# Sheet1.net
KiCad netlist of a schematic drawn in Altium Designer
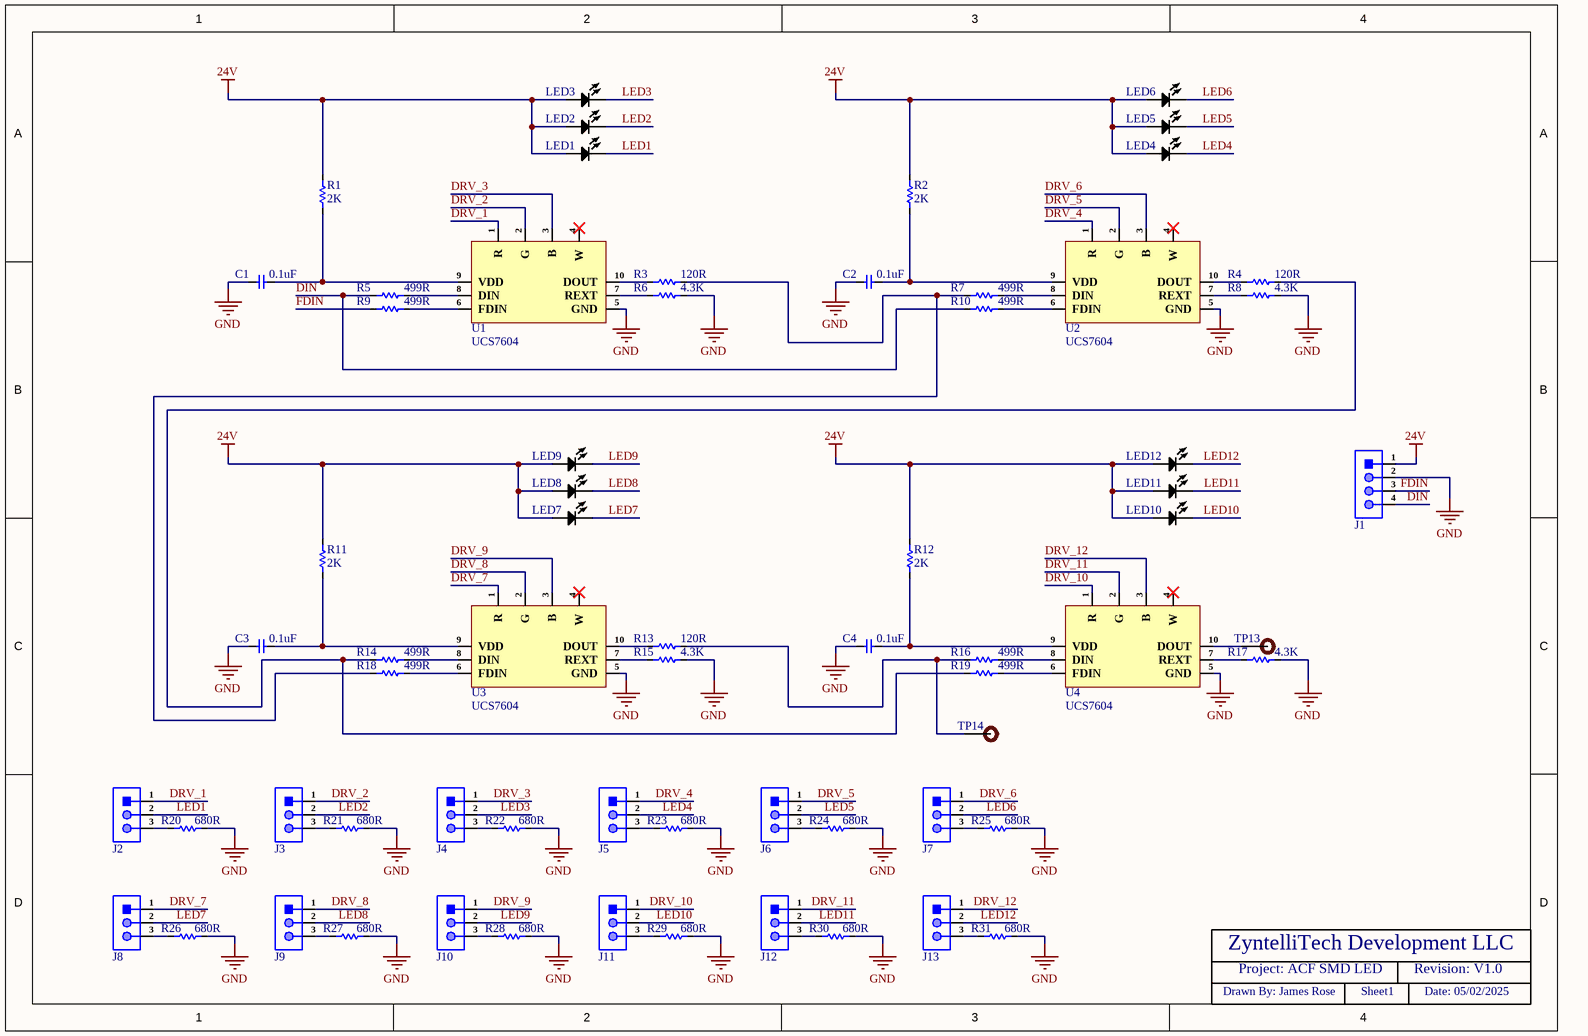
[diagram p0: Sheet1.SchDoc]

(export (version "E")
  (design (tool "Eeschema 10.0.6"))
  (components
    (comp (ref "C1")
      (value "0.1uF")
      (footprint "Cap-0603")
      (description "CAP CER 0.1UF 50V X7R 0603")
      (fields (field (name "LCSC PART NUMBER") "C91183") (field (name "MANUFACTURER") "Yageo"))
      (libsource (lib "eSpark Libraries") (part "CC0603JRX7R9BB104"))
    )
    (comp (ref "C2")
      (value "0.1uF")
      (footprint "Cap-0603")
      (description "CAP CER 0.1UF 50V X7R 0603")
      (fields (field (name "LCSC PART NUMBER") "C91183") (field (name "MANUFACTURER") "Yageo"))
      (libsource (lib "eSpark Libraries") (part "CC0603JRX7R9BB104"))
    )
    (comp (ref "C3")
      (value "0.1uF")
      (footprint "Cap-0603")
      (description "CAP CER 0.1UF 50V X7R 0603")
      (fields (field (name "LCSC PART NUMBER") "C91183") (field (name "MANUFACTURER") "Yageo"))
      (libsource (lib "eSpark Libraries") (part "CC0603JRX7R9BB104"))
    )
    (comp (ref "C4")
      (value "0.1uF")
      (footprint "Cap-0603")
      (description "CAP CER 0.1UF 50V X7R 0603")
      (fields (field (name "LCSC PART NUMBER") "C91183") (field (name "MANUFACTURER") "Yageo"))
      (libsource (lib "eSpark Libraries") (part "CC0603JRX7R9BB104"))
    )
    (comp (ref "J1")
      (value "X6511WV-04H-C60D30")
      (footprint "HDR1X4_")
      (fields (field (name "MANUFACTURER") "XKB") (field (name "LCSC PART NUMBER") "C706876"))
      (libsource (lib "eSpark Libraries") (part "X6511WV-04H-C60D30"))
    )
    (comp (ref "J2")
      (value "X6511WV-03H-C60D30")
      (footprint "HDR1X3_")
      (fields (field (name "MANUFACTURER") "XKB") (field (name "LCSC PART NUMBER") "C706875"))
      (libsource (lib "eSpark Libraries") (part "X6511WV-03H-C60D30"))
    )
    (comp (ref "J3")
      (value "X6511WV-03H-C60D30")
      (footprint "HDR1X3_")
      (fields (field (name "MANUFACTURER") "XKB") (field (name "LCSC PART NUMBER") "C706875"))
      (libsource (lib "eSpark Libraries") (part "X6511WV-03H-C60D30"))
    )
    (comp (ref "J4")
      (value "X6511WV-03H-C60D30")
      (footprint "HDR1X3_")
      (fields (field (name "MANUFACTURER") "XKB") (field (name "LCSC PART NUMBER") "C706875"))
      (libsource (lib "eSpark Libraries") (part "X6511WV-03H-C60D30"))
    )
    (comp (ref "J5")
      (value "X6511WV-03H-C60D30")
      (footprint "HDR1X3_")
      (fields (field (name "MANUFACTURER") "XKB") (field (name "LCSC PART NUMBER") "C706875"))
      (libsource (lib "eSpark Libraries") (part "X6511WV-03H-C60D30"))
    )
    (comp (ref "J6")
      (value "X6511WV-03H-C60D30")
      (footprint "HDR1X3_")
      (fields (field (name "MANUFACTURER") "XKB") (field (name "LCSC PART NUMBER") "C706875"))
      (libsource (lib "eSpark Libraries") (part "X6511WV-03H-C60D30"))
    )
    (comp (ref "J7")
      (value "X6511WV-03H-C60D30")
      (footprint "HDR1X3_")
      (fields (field (name "MANUFACTURER") "XKB") (field (name "LCSC PART NUMBER") "C706875"))
      (libsource (lib "eSpark Libraries") (part "X6511WV-03H-C60D30"))
    )
    (comp (ref "J8")
      (value "X6511WV-03H-C60D30")
      (footprint "HDR1X3_")
      (fields (field (name "MANUFACTURER") "XKB") (field (name "LCSC PART NUMBER") "C706875"))
      (libsource (lib "eSpark Libraries") (part "X6511WV-03H-C60D30"))
    )
    (comp (ref "J9")
      (value "X6511WV-03H-C60D30")
      (footprint "HDR1X3_")
      (fields (field (name "MANUFACTURER") "XKB") (field (name "LCSC PART NUMBER") "C706875"))
      (libsource (lib "eSpark Libraries") (part "X6511WV-03H-C60D30"))
    )
    (comp (ref "J10")
      (value "X6511WV-03H-C60D30")
      (footprint "HDR1X3_")
      (fields (field (name "MANUFACTURER") "XKB") (field (name "LCSC PART NUMBER") "C706875"))
      (libsource (lib "eSpark Libraries") (part "X6511WV-03H-C60D30"))
    )
    (comp (ref "J11")
      (value "X6511WV-03H-C60D30")
      (footprint "HDR1X3_")
      (fields (field (name "MANUFACTURER") "XKB") (field (name "LCSC PART NUMBER") "C706875"))
      (libsource (lib "eSpark Libraries") (part "X6511WV-03H-C60D30"))
    )
    (comp (ref "J12")
      (value "X6511WV-03H-C60D30")
      (footprint "HDR1X3_")
      (fields (field (name "MANUFACTURER") "XKB") (field (name "LCSC PART NUMBER") "C706875"))
      (libsource (lib "eSpark Libraries") (part "X6511WV-03H-C60D30"))
    )
    (comp (ref "J13")
      (value "X6511WV-03H-C60D30")
      (footprint "HDR1X3_")
      (fields (field (name "MANUFACTURER") "XKB") (field (name "LCSC PART NUMBER") "C706875"))
      (libsource (lib "eSpark Libraries") (part "X6511WV-03H-C60D30"))
    )
    (comp (ref "LED1")
      (value "5050 LED")
      (footprint "5050 LED")
      (libsource (lib "eSpark Libraries") (part "5050 LED"))
    )
    (comp (ref "LED2")
      (value "5050 LED")
      (footprint "5050 LED")
      (libsource (lib "eSpark Libraries") (part "5050 LED"))
    )
    (comp (ref "LED3")
      (value "5050 LED")
      (footprint "5050 LED")
      (libsource (lib "eSpark Libraries") (part "5050 LED"))
    )
    (comp (ref "LED4")
      (value "5050 LED")
      (footprint "5050 LED")
      (libsource (lib "eSpark Libraries") (part "5050 LED"))
    )
    (comp (ref "LED5")
      (value "5050 LED")
      (footprint "5050 LED")
      (libsource (lib "eSpark Libraries") (part "5050 LED"))
    )
    (comp (ref "LED6")
      (value "5050 LED")
      (footprint "5050 LED")
      (libsource (lib "eSpark Libraries") (part "5050 LED"))
    )
    (comp (ref "LED7")
      (value "5050 LED")
      (footprint "5050 LED")
      (libsource (lib "eSpark Libraries") (part "5050 LED"))
    )
    (comp (ref "LED8")
      (value "5050 LED")
      (footprint "5050 LED")
      (libsource (lib "eSpark Libraries") (part "5050 LED"))
    )
    (comp (ref "LED9")
      (value "5050 LED")
      (footprint "5050 LED")
      (libsource (lib "eSpark Libraries") (part "5050 LED"))
    )
    (comp (ref "LED10")
      (value "5050 LED")
      (footprint "5050 LED")
      (libsource (lib "eSpark Libraries") (part "5050 LED"))
    )
    (comp (ref "LED11")
      (value "5050 LED")
      (footprint "5050 LED")
      (libsource (lib "eSpark Libraries") (part "5050 LED"))
    )
    (comp (ref "LED12")
      (value "5050 LED")
      (footprint "5050 LED")
      (libsource (lib "eSpark Libraries") (part "5050 LED"))
    )
    (comp (ref "R1")
      (value "2K")
      (footprint "Res-1206")
      (description "RES 2K OHM 1% 1/4W 1206")
      (fields (field (name "LCSC PART NUMBER") "C133543") (field (name "MANUFACTURER") "Yageo"))
      (libsource (lib "eSpark Libraries") (part "RC1206FR-072KL"))
    )
    (comp (ref "R2")
      (value "2K")
      (footprint "Res-1206")
      (description "RES 2K OHM 1% 1/4W 1206")
      (fields (field (name "LCSC PART NUMBER") "C133543") (field (name "MANUFACTURER") "Yageo"))
      (libsource (lib "eSpark Libraries") (part "RC1206FR-072KL"))
    )
    (comp (ref "R3")
      (value "120R")
      (footprint "Res-0603")
      (description "RES 120 OHM 1% 1/10W 0603")
      (fields
        (field (name "MANUFACTURER") "Yageo")
        (field (name "MANUFACTURER PART NUMBER") "RC0603FR-07120RL")
      )
      (libsource (lib "eSpark Libraries") (part "RC0603FR-07120RL"))
    )
    (comp (ref "R4")
      (value "120R")
      (footprint "Res-0603")
      (description "RES 120 OHM 1% 1/10W 0603")
      (fields
        (field (name "MANUFACTURER") "Yageo")
        (field (name "MANUFACTURER PART NUMBER") "RC0603FR-07120RL")
      )
      (libsource (lib "eSpark Libraries") (part "RC0603FR-07120RL"))
    )
    (comp (ref "R5")
      (value "499R")
      (footprint "Res-0603")
      (description "RES 499 OHM 1% 1/10W 0603")
      (fields
        (field (name "MANUFACTURER") "Yageo")
        (field (name "MANUFACTURER PART NUMBER") "RC0603FR-07499RL")
      )
      (libsource (lib "eSpark Libraries") (part "RC0603FR-07499RL"))
    )
    (comp (ref "R6")
      (value "4.3K")
      (footprint "Res-0402")
      (description "RES 4.3K OHM 1% 1/16W 0402")
      (fields (field (name "LCSC PART NUMBER") "C477725") (field (name "MANUFACTURER") "Yageo"))
      (libsource (lib "eSpark Libraries") (part "RC0402FR-074K3L"))
    )
    (comp (ref "R7")
      (value "499R")
      (footprint "Res-0603")
      (description "RES 499 OHM 1% 1/10W 0603")
      (fields
        (field (name "MANUFACTURER") "Yageo")
        (field (name "MANUFACTURER PART NUMBER") "RC0603FR-07499RL")
      )
      (libsource (lib "eSpark Libraries") (part "RC0603FR-07499RL"))
    )
    (comp (ref "R8")
      (value "4.3K")
      (footprint "Res-0402")
      (description "RES 4.3K OHM 1% 1/16W 0402")
      (fields (field (name "LCSC PART NUMBER") "C477725") (field (name "MANUFACTURER") "Yageo"))
      (libsource (lib "eSpark Libraries") (part "RC0402FR-074K3L"))
    )
    (comp (ref "R9")
      (value "499R")
      (footprint "Res-0603")
      (description "RES 499 OHM 1% 1/10W 0603")
      (fields
        (field (name "MANUFACTURER") "Yageo")
        (field (name "MANUFACTURER PART NUMBER") "RC0603FR-07499RL")
      )
      (libsource (lib "eSpark Libraries") (part "RC0603FR-07499RL"))
    )
    (comp (ref "R10")
      (value "499R")
      (footprint "Res-0603")
      (description "RES 499 OHM 1% 1/10W 0603")
      (fields
        (field (name "MANUFACTURER") "Yageo")
        (field (name "MANUFACTURER PART NUMBER") "RC0603FR-07499RL")
      )
      (libsource (lib "eSpark Libraries") (part "RC0603FR-07499RL"))
    )
    (comp (ref "R11")
      (value "2K")
      (footprint "Res-1206")
      (description "RES 2K OHM 1% 1/4W 1206")
      (fields (field (name "LCSC PART NUMBER") "C133543") (field (name "MANUFACTURER") "Yageo"))
      (libsource (lib "eSpark Libraries") (part "RC1206FR-072KL"))
    )
    (comp (ref "R12")
      (value "2K")
      (footprint "Res-1206")
      (description "RES 2K OHM 1% 1/4W 1206")
      (fields (field (name "LCSC PART NUMBER") "C133543") (field (name "MANUFACTURER") "Yageo"))
      (libsource (lib "eSpark Libraries") (part "RC1206FR-072KL"))
    )
    (comp (ref "R13")
      (value "120R")
      (footprint "Res-0603")
      (description "RES 120 OHM 1% 1/10W 0603")
      (fields
        (field (name "MANUFACTURER") "Yageo")
        (field (name "MANUFACTURER PART NUMBER") "RC0603FR-07120RL")
      )
      (libsource (lib "eSpark Libraries") (part "RC0603FR-07120RL"))
    )
    (comp (ref "R14")
      (value "499R")
      (footprint "Res-0603")
      (description "RES 499 OHM 1% 1/10W 0603")
      (fields
        (field (name "MANUFACTURER") "Yageo")
        (field (name "MANUFACTURER PART NUMBER") "RC0603FR-07499RL")
      )
      (libsource (lib "eSpark Libraries") (part "RC0603FR-07499RL"))
    )
    (comp (ref "R15")
      (value "4.3K")
      (footprint "Res-0402")
      (description "RES 4.3K OHM 1% 1/16W 0402")
      (fields (field (name "LCSC PART NUMBER") "C477725") (field (name "MANUFACTURER") "Yageo"))
      (libsource (lib "eSpark Libraries") (part "RC0402FR-074K3L"))
    )
    (comp (ref "R16")
      (value "499R")
      (footprint "Res-0603")
      (description "RES 499 OHM 1% 1/10W 0603")
      (fields
        (field (name "MANUFACTURER") "Yageo")
        (field (name "MANUFACTURER PART NUMBER") "RC0603FR-07499RL")
      )
      (libsource (lib "eSpark Libraries") (part "RC0603FR-07499RL"))
    )
    (comp (ref "R17")
      (value "4.3K")
      (footprint "Res-0402")
      (description "RES 4.3K OHM 1% 1/16W 0402")
      (fields (field (name "LCSC PART NUMBER") "C477725") (field (name "MANUFACTURER") "Yageo"))
      (libsource (lib "eSpark Libraries") (part "RC0402FR-074K3L"))
    )
    (comp (ref "R18")
      (value "499R")
      (footprint "Res-0603")
      (description "RES 499 OHM 1% 1/10W 0603")
      (fields
        (field (name "MANUFACTURER") "Yageo")
        (field (name "MANUFACTURER PART NUMBER") "RC0603FR-07499RL")
      )
      (libsource (lib "eSpark Libraries") (part "RC0603FR-07499RL"))
    )
    (comp (ref "R19")
      (value "499R")
      (footprint "Res-0603")
      (description "RES 499 OHM 1% 1/10W 0603")
      (fields
        (field (name "MANUFACTURER") "Yageo")
        (field (name "MANUFACTURER PART NUMBER") "RC0603FR-07499RL")
      )
      (libsource (lib "eSpark Libraries") (part "RC0603FR-07499RL"))
    )
    (comp (ref "R20")
      (value "680R")
      (footprint "Res-0603")
      (description "RES SMD 680 OHM 1% 1/10W 0603")
      (fields
        (field (name "MANUFACTURER") "Yageo")
        (field (name "MANUFACTURER PART NUMBER") "RC0603FR-07680RL")
      )
      (libsource (lib "eSpark Libraries") (part "RC0603FR-07680RL"))
    )
    (comp (ref "R21")
      (value "680R")
      (footprint "Res-0603")
      (description "RES SMD 680 OHM 1% 1/10W 0603")
      (fields
        (field (name "MANUFACTURER") "Yageo")
        (field (name "MANUFACTURER PART NUMBER") "RC0603FR-07680RL")
      )
      (libsource (lib "eSpark Libraries") (part "RC0603FR-07680RL"))
    )
    (comp (ref "R22")
      (value "680R")
      (footprint "Res-0603")
      (description "RES SMD 680 OHM 1% 1/10W 0603")
      (fields
        (field (name "MANUFACTURER") "Yageo")
        (field (name "MANUFACTURER PART NUMBER") "RC0603FR-07680RL")
      )
      (libsource (lib "eSpark Libraries") (part "RC0603FR-07680RL"))
    )
    (comp (ref "R23")
      (value "680R")
      (footprint "Res-0603")
      (description "RES SMD 680 OHM 1% 1/10W 0603")
      (fields
        (field (name "MANUFACTURER") "Yageo")
        (field (name "MANUFACTURER PART NUMBER") "RC0603FR-07680RL")
      )
      (libsource (lib "eSpark Libraries") (part "RC0603FR-07680RL"))
    )
    (comp (ref "R24")
      (value "680R")
      (footprint "Res-0603")
      (description "RES SMD 680 OHM 1% 1/10W 0603")
      (fields
        (field (name "MANUFACTURER") "Yageo")
        (field (name "MANUFACTURER PART NUMBER") "RC0603FR-07680RL")
      )
      (libsource (lib "eSpark Libraries") (part "RC0603FR-07680RL"))
    )
    (comp (ref "R25")
      (value "680R")
      (footprint "Res-0603")
      (description "RES SMD 680 OHM 1% 1/10W 0603")
      (fields
        (field (name "MANUFACTURER") "Yageo")
        (field (name "MANUFACTURER PART NUMBER") "RC0603FR-07680RL")
      )
      (libsource (lib "eSpark Libraries") (part "RC0603FR-07680RL"))
    )
    (comp (ref "R26")
      (value "680R")
      (footprint "Res-0603")
      (description "RES SMD 680 OHM 1% 1/10W 0603")
      (fields
        (field (name "MANUFACTURER") "Yageo")
        (field (name "MANUFACTURER PART NUMBER") "RC0603FR-07680RL")
      )
      (libsource (lib "eSpark Libraries") (part "RC0603FR-07680RL"))
    )
    (comp (ref "R27")
      (value "680R")
      (footprint "Res-0603")
      (description "RES SMD 680 OHM 1% 1/10W 0603")
      (fields
        (field (name "MANUFACTURER") "Yageo")
        (field (name "MANUFACTURER PART NUMBER") "RC0603FR-07680RL")
      )
      (libsource (lib "eSpark Libraries") (part "RC0603FR-07680RL"))
    )
    (comp (ref "R28")
      (value "680R")
      (footprint "Res-0603")
      (description "RES SMD 680 OHM 1% 1/10W 0603")
      (fields
        (field (name "MANUFACTURER") "Yageo")
        (field (name "MANUFACTURER PART NUMBER") "RC0603FR-07680RL")
      )
      (libsource (lib "eSpark Libraries") (part "RC0603FR-07680RL"))
    )
    (comp (ref "R29")
      (value "680R")
      (footprint "Res-0603")
      (description "RES SMD 680 OHM 1% 1/10W 0603")
      (fields
        (field (name "MANUFACTURER") "Yageo")
        (field (name "MANUFACTURER PART NUMBER") "RC0603FR-07680RL")
      )
      (libsource (lib "eSpark Libraries") (part "RC0603FR-07680RL"))
    )
    (comp (ref "R30")
      (value "680R")
      (footprint "Res-0603")
      (description "RES SMD 680 OHM 1% 1/10W 0603")
      (fields
        (field (name "MANUFACTURER") "Yageo")
        (field (name "MANUFACTURER PART NUMBER") "RC0603FR-07680RL")
      )
      (libsource (lib "eSpark Libraries") (part "RC0603FR-07680RL"))
    )
    (comp (ref "R31")
      (value "680R")
      (footprint "Res-0603")
      (description "RES SMD 680 OHM 1% 1/10W 0603")
      (fields
        (field (name "MANUFACTURER") "Yageo")
        (field (name "MANUFACTURER PART NUMBER") "RC0603FR-07680RL")
      )
      (libsource (lib "eSpark Libraries") (part "RC0603FR-07680RL"))
    )
    (comp (ref "TP13")
      (value "0.5mm Test Pad")
      (footprint "0.5mm Test Pad")
      (description "Test pad")
      (libsource (lib "eSpark Libraries") (part "0.5mm Test Pad"))
    )
    (comp (ref "TP14")
      (value "0.5mm Test Pad")
      (footprint "0.5mm Test Pad")
      (description "Test pad")
      (libsource (lib "eSpark Libraries") (part "0.5mm Test Pad"))
    )
    (comp (ref "U1")
      (value "UCS7604")
      (footprint "SOP-10")
      (description "RGBW LED Driver")
      (fields (field (name "MANUFACTURER") "UCS"))
      (libsource (lib "eSpark Libraries") (part "UCS7604"))
    )
    (comp (ref "U2")
      (value "UCS7604")
      (footprint "SOP-10")
      (description "RGBW LED Driver")
      (fields (field (name "MANUFACTURER") "UCS"))
      (libsource (lib "eSpark Libraries") (part "UCS7604"))
    )
    (comp (ref "U3")
      (value "UCS7604")
      (footprint "SOP-10")
      (description "RGBW LED Driver")
      (fields (field (name "MANUFACTURER") "UCS"))
      (libsource (lib "eSpark Libraries") (part "UCS7604"))
    )
    (comp (ref "U4")
      (value "UCS7604")
      (footprint "SOP-10")
      (description "RGBW LED Driver")
      (fields (field (name "MANUFACTURER") "UCS"))
      (libsource (lib "eSpark Libraries") (part "UCS7604"))
    )
  )
  (nets
    (net (code "1") (name "/DIN") (class "Default")
      (node (ref "J1") (pin "4") (pinfunction "4_4") (pintype "passive"))
      (node (ref "R10") (pin "1") (pinfunction "1_1") (pintype "passive"))
      (node (ref "R5") (pin "1") (pinfunction "1_1") (pintype "passive"))
    )
    (net (code "2") (name "/DRV_1") (class "Default")
      (node (ref "J2") (pin "1") (pinfunction "1_1") (pintype "passive"))
      (node (ref "U1") (pin "1") (pinfunction "R_1") (pintype "passive"))
    )
    (net (code "3") (name "/DRV_2") (class "Default")
      (node (ref "J3") (pin "1") (pinfunction "1_1") (pintype "passive"))
      (node (ref "U1") (pin "2") (pinfunction "G_2") (pintype "passive"))
    )
    (net (code "4") (name "/DRV_3") (class "Default")
      (node (ref "J4") (pin "1") (pinfunction "1_1") (pintype "passive"))
      (node (ref "U1") (pin "3") (pinfunction "B_3") (pintype "passive"))
    )
    (net (code "5") (name "/DRV_4") (class "Default")
      (node (ref "J5") (pin "1") (pinfunction "1_1") (pintype "passive"))
      (node (ref "U2") (pin "1") (pinfunction "R_1") (pintype "passive"))
    )
    (net (code "6") (name "/DRV_5") (class "Default")
      (node (ref "J6") (pin "1") (pinfunction "1_1") (pintype "passive"))
      (node (ref "U2") (pin "2") (pinfunction "G_2") (pintype "passive"))
    )
    (net (code "7") (name "/DRV_6") (class "Default")
      (node (ref "J7") (pin "1") (pinfunction "1_1") (pintype "passive"))
      (node (ref "U2") (pin "3") (pinfunction "B_3") (pintype "passive"))
    )
    (net (code "8") (name "/DRV_7") (class "Default")
      (node (ref "J8") (pin "1") (pinfunction "1_1") (pintype "passive"))
      (node (ref "U3") (pin "1") (pinfunction "R_1") (pintype "passive"))
    )
    (net (code "9") (name "/DRV_8") (class "Default")
      (node (ref "J9") (pin "1") (pinfunction "1_1") (pintype "passive"))
      (node (ref "U3") (pin "2") (pinfunction "G_2") (pintype "passive"))
    )
    (net (code "10") (name "/DRV_9") (class "Default")
      (node (ref "J10") (pin "1") (pinfunction "1_1") (pintype "passive"))
      (node (ref "U3") (pin "3") (pinfunction "B_3") (pintype "passive"))
    )
    (net (code "11") (name "/DRV_10") (class "Default")
      (node (ref "J11") (pin "1") (pinfunction "1_1") (pintype "passive"))
      (node (ref "U4") (pin "1") (pinfunction "R_1") (pintype "passive"))
    )
    (net (code "12") (name "/DRV_11") (class "Default")
      (node (ref "J12") (pin "1") (pinfunction "1_1") (pintype "passive"))
      (node (ref "U4") (pin "2") (pinfunction "G_2") (pintype "passive"))
    )
    (net (code "13") (name "/DRV_12") (class "Default")
      (node (ref "J13") (pin "1") (pinfunction "1_1") (pintype "passive"))
      (node (ref "U4") (pin "3") (pinfunction "B_3") (pintype "passive"))
    )
    (net (code "14") (name "/FDIN") (class "Default")
      (node (ref "J1") (pin "3") (pinfunction "3_3") (pintype "passive"))
      (node (ref "R9") (pin "1") (pinfunction "1_1") (pintype "passive"))
    )
    (net (code "15") (name "/LED1") (class "Default")
      (node (ref "J2") (pin "2") (pinfunction "2_2") (pintype "passive"))
      (node (ref "LED1") (pin "K") (pinfunction "K_K") (pintype "passive"))
    )
    (net (code "16") (name "/LED2") (class "Default")
      (node (ref "J3") (pin "2") (pinfunction "2_2") (pintype "passive"))
      (node (ref "LED2") (pin "K") (pinfunction "K_K") (pintype "passive"))
    )
    (net (code "17") (name "/LED3") (class "Default")
      (node (ref "J4") (pin "2") (pinfunction "2_2") (pintype "passive"))
      (node (ref "LED3") (pin "K") (pinfunction "K_K") (pintype "passive"))
    )
    (net (code "18") (name "/LED4") (class "Default")
      (node (ref "J5") (pin "2") (pinfunction "2_2") (pintype "passive"))
      (node (ref "LED4") (pin "K") (pinfunction "K_K") (pintype "passive"))
    )
    (net (code "19") (name "/LED5") (class "Default")
      (node (ref "J6") (pin "2") (pinfunction "2_2") (pintype "passive"))
      (node (ref "LED5") (pin "K") (pinfunction "K_K") (pintype "passive"))
    )
    (net (code "20") (name "/LED6") (class "Default")
      (node (ref "J7") (pin "2") (pinfunction "2_2") (pintype "passive"))
      (node (ref "LED6") (pin "K") (pinfunction "K_K") (pintype "passive"))
    )
    (net (code "21") (name "/LED7") (class "Default")
      (node (ref "J8") (pin "2") (pinfunction "2_2") (pintype "passive"))
      (node (ref "LED7") (pin "K") (pinfunction "K_K") (pintype "passive"))
    )
    (net (code "22") (name "/LED8") (class "Default")
      (node (ref "J9") (pin "2") (pinfunction "2_2") (pintype "passive"))
      (node (ref "LED8") (pin "K") (pinfunction "K_K") (pintype "passive"))
    )
    (net (code "23") (name "/LED9") (class "Default")
      (node (ref "J10") (pin "2") (pinfunction "2_2") (pintype "passive"))
      (node (ref "LED9") (pin "K") (pinfunction "K_K") (pintype "passive"))
    )
    (net (code "24") (name "/LED10") (class "Default")
      (node (ref "J11") (pin "2") (pinfunction "2_2") (pintype "passive"))
      (node (ref "LED10") (pin "K") (pinfunction "K_K") (pintype "passive"))
    )
    (net (code "25") (name "/LED11") (class "Default")
      (node (ref "J12") (pin "2") (pinfunction "2_2") (pintype "passive"))
      (node (ref "LED11") (pin "K") (pinfunction "K_K") (pintype "passive"))
    )
    (net (code "26") (name "/LED12") (class "Default")
      (node (ref "J13") (pin "2") (pinfunction "2_2") (pintype "passive"))
      (node (ref "LED12") (pin "K") (pinfunction "K_K") (pintype "passive"))
    )
    (net (code "27") (name "24V") (class "Default")
      (node (ref "J1") (pin "1") (pinfunction "1_1") (pintype "passive"))
      (node (ref "LED1") (pin "A") (pinfunction "A_A") (pintype "passive"))
      (node (ref "LED10") (pin "A") (pinfunction "A_A") (pintype "passive"))
      (node (ref "LED11") (pin "A") (pinfunction "A_A") (pintype "passive"))
      (node (ref "LED12") (pin "A") (pinfunction "A_A") (pintype "passive"))
      (node (ref "LED2") (pin "A") (pinfunction "A_A") (pintype "passive"))
      (node (ref "LED3") (pin "A") (pinfunction "A_A") (pintype "passive"))
      (node (ref "LED4") (pin "A") (pinfunction "A_A") (pintype "passive"))
      (node (ref "LED5") (pin "A") (pinfunction "A_A") (pintype "passive"))
      (node (ref "LED6") (pin "A") (pinfunction "A_A") (pintype "passive"))
      (node (ref "LED7") (pin "A") (pinfunction "A_A") (pintype "passive"))
      (node (ref "LED8") (pin "A") (pinfunction "A_A") (pintype "passive"))
      (node (ref "LED9") (pin "A") (pinfunction "A_A") (pintype "passive"))
      (node (ref "R1") (pin "2") (pinfunction "2_2") (pintype "passive"))
      (node (ref "R11") (pin "2") (pinfunction "2_2") (pintype "passive"))
      (node (ref "R12") (pin "2") (pinfunction "2_2") (pintype "passive"))
      (node (ref "R2") (pin "2") (pinfunction "2_2") (pintype "passive"))
    )
    (net (code "28") (name "GND") (class "Default")
      (node (ref "C1") (pin "1") (pinfunction "1_1") (pintype "passive"))
      (node (ref "C2") (pin "1") (pinfunction "1_1") (pintype "passive"))
      (node (ref "C3") (pin "1") (pinfunction "1_1") (pintype "passive"))
      (node (ref "C4") (pin "1") (pinfunction "1_1") (pintype "passive"))
      (node (ref "J1") (pin "2") (pinfunction "2_2") (pintype "passive"))
      (node (ref "R15") (pin "2") (pinfunction "2_2") (pintype "passive"))
      (node (ref "R17") (pin "2") (pinfunction "2_2") (pintype "passive"))
      (node (ref "R20") (pin "2") (pinfunction "2_2") (pintype "passive"))
      (node (ref "R21") (pin "2") (pinfunction "2_2") (pintype "passive"))
      (node (ref "R22") (pin "2") (pinfunction "2_2") (pintype "passive"))
      (node (ref "R23") (pin "2") (pinfunction "2_2") (pintype "passive"))
      (node (ref "R24") (pin "2") (pinfunction "2_2") (pintype "passive"))
      (node (ref "R25") (pin "2") (pinfunction "2_2") (pintype "passive"))
      (node (ref "R26") (pin "2") (pinfunction "2_2") (pintype "passive"))
      (node (ref "R27") (pin "2") (pinfunction "2_2") (pintype "passive"))
      (node (ref "R28") (pin "2") (pinfunction "2_2") (pintype "passive"))
      (node (ref "R29") (pin "2") (pinfunction "2_2") (pintype "passive"))
      (node (ref "R30") (pin "2") (pinfunction "2_2") (pintype "passive"))
      (node (ref "R31") (pin "2") (pinfunction "2_2") (pintype "passive"))
      (node (ref "R6") (pin "2") (pinfunction "2_2") (pintype "passive"))
      (node (ref "R8") (pin "2") (pinfunction "2_2") (pintype "passive"))
      (node (ref "U1") (pin "5") (pinfunction "GND_5") (pintype "passive"))
      (node (ref "U2") (pin "5") (pinfunction "GND_5") (pintype "passive"))
      (node (ref "U3") (pin "5") (pinfunction "GND_5") (pintype "passive"))
      (node (ref "U4") (pin "5") (pinfunction "GND_5") (pintype "passive"))
    )
    (net (code "29") (name "Net-(J2-Pad3)") (class "Default")
      (node (ref "J2") (pin "3") (pinfunction "3_3") (pintype "passive"))
      (node (ref "R20") (pin "1") (pinfunction "1_1") (pintype "passive"))
    )
    (net (code "30") (name "Net-(J3-Pad3)") (class "Default")
      (node (ref "J3") (pin "3") (pinfunction "3_3") (pintype "passive"))
      (node (ref "R21") (pin "1") (pinfunction "1_1") (pintype "passive"))
    )
    (net (code "31") (name "Net-(J4-Pad3)") (class "Default")
      (node (ref "J4") (pin "3") (pinfunction "3_3") (pintype "passive"))
      (node (ref "R22") (pin "1") (pinfunction "1_1") (pintype "passive"))
    )
    (net (code "32") (name "Net-(J5-Pad3)") (class "Default")
      (node (ref "J5") (pin "3") (pinfunction "3_3") (pintype "passive"))
      (node (ref "R23") (pin "1") (pinfunction "1_1") (pintype "passive"))
    )
    (net (code "33") (name "Net-(J6-Pad3)") (class "Default")
      (node (ref "J6") (pin "3") (pinfunction "3_3") (pintype "passive"))
      (node (ref "R24") (pin "1") (pinfunction "1_1") (pintype "passive"))
    )
    (net (code "34") (name "Net-(J7-Pad3)") (class "Default")
      (node (ref "J7") (pin "3") (pinfunction "3_3") (pintype "passive"))
      (node (ref "R25") (pin "1") (pinfunction "1_1") (pintype "passive"))
    )
    (net (code "35") (name "Net-(J8-Pad3)") (class "Default")
      (node (ref "J8") (pin "3") (pinfunction "3_3") (pintype "passive"))
      (node (ref "R26") (pin "1") (pinfunction "1_1") (pintype "passive"))
    )
    (net (code "36") (name "Net-(J9-Pad3)") (class "Default")
      (node (ref "J9") (pin "3") (pinfunction "3_3") (pintype "passive"))
      (node (ref "R27") (pin "1") (pinfunction "1_1") (pintype "passive"))
    )
    (net (code "37") (name "Net-(J10-Pad3)") (class "Default")
      (node (ref "J10") (pin "3") (pinfunction "3_3") (pintype "passive"))
      (node (ref "R28") (pin "1") (pinfunction "1_1") (pintype "passive"))
    )
    (net (code "38") (name "Net-(J11-Pad3)") (class "Default")
      (node (ref "J11") (pin "3") (pinfunction "3_3") (pintype "passive"))
      (node (ref "R29") (pin "1") (pinfunction "1_1") (pintype "passive"))
    )
    (net (code "39") (name "Net-(J12-Pad3)") (class "Default")
      (node (ref "J12") (pin "3") (pinfunction "3_3") (pintype "passive"))
      (node (ref "R30") (pin "1") (pinfunction "1_1") (pintype "passive"))
    )
    (net (code "40") (name "Net-(J13-Pad3)") (class "Default")
      (node (ref "J13") (pin "3") (pinfunction "3_3") (pintype "passive"))
      (node (ref "R31") (pin "1") (pinfunction "1_1") (pintype "passive"))
    )
    (net (code "41") (name "Net-(R13-Pad2)") (class "Default")
      (node (ref "R13") (pin "2") (pinfunction "2_2") (pintype "passive"))
      (node (ref "R16") (pin "1") (pinfunction "1_1") (pintype "passive"))
      (node (ref "TP14") (pin "1") (pinfunction "1_1") (pintype "passive"))
    )
    (net (code "42") (name "Net-(R14-Pad1)") (class "Default")
      (node (ref "R14") (pin "1") (pinfunction "1_1") (pintype "passive"))
      (node (ref "R19") (pin "1") (pinfunction "1_1") (pintype "passive"))
      (node (ref "R4") (pin "2") (pinfunction "2_2") (pintype "passive"))
    )
    (net (code "43") (name "Net-(R18-Pad1)") (class "Default")
      (node (ref "R18") (pin "1") (pinfunction "1_1") (pintype "passive"))
      (node (ref "R3") (pin "2") (pinfunction "2_2") (pintype "passive"))
      (node (ref "R7") (pin "1") (pinfunction "1_1") (pintype "passive"))
    )
    (net (code "44") (name "Net-(U1-DIN)") (class "Default")
      (node (ref "R5") (pin "2") (pinfunction "2_2") (pintype "passive"))
      (node (ref "U1") (pin "8") (pinfunction "DIN_8") (pintype "passive"))
    )
    (net (code "45") (name "Net-(U1-DOUT)") (class "Default")
      (node (ref "R3") (pin "1") (pinfunction "1_1") (pintype "passive"))
      (node (ref "U1") (pin "10") (pinfunction "DOUT_10") (pintype "passive"))
    )
    (net (code "46") (name "Net-(U1-FDIN)") (class "Default")
      (node (ref "R9") (pin "2") (pinfunction "2_2") (pintype "passive"))
      (node (ref "U1") (pin "6") (pinfunction "FDIN_6") (pintype "passive"))
    )
    (net (code "47") (name "Net-(U1-REXT)") (class "Default")
      (node (ref "R6") (pin "1") (pinfunction "1_1") (pintype "passive"))
      (node (ref "U1") (pin "7") (pinfunction "REXT_7") (pintype "passive"))
    )
    (net (code "48") (name "Net-(U1-VDD)") (class "Default")
      (node (ref "C1") (pin "2") (pinfunction "2_2") (pintype "passive"))
      (node (ref "R1") (pin "1") (pinfunction "1_1") (pintype "passive"))
      (node (ref "U1") (pin "9") (pinfunction "VDD_9") (pintype "passive"))
    )
    (net (code "49") (name "Net-(U2-DIN)") (class "Default")
      (node (ref "R7") (pin "2") (pinfunction "2_2") (pintype "passive"))
      (node (ref "U2") (pin "8") (pinfunction "DIN_8") (pintype "passive"))
    )
    (net (code "50") (name "Net-(U2-DOUT)") (class "Default")
      (node (ref "R4") (pin "1") (pinfunction "1_1") (pintype "passive"))
      (node (ref "U2") (pin "10") (pinfunction "DOUT_10") (pintype "passive"))
    )
    (net (code "51") (name "Net-(U2-FDIN)") (class "Default")
      (node (ref "R10") (pin "2") (pinfunction "2_2") (pintype "passive"))
      (node (ref "U2") (pin "6") (pinfunction "FDIN_6") (pintype "passive"))
    )
    (net (code "52") (name "Net-(U2-REXT)") (class "Default")
      (node (ref "R8") (pin "1") (pinfunction "1_1") (pintype "passive"))
      (node (ref "U2") (pin "7") (pinfunction "REXT_7") (pintype "passive"))
    )
    (net (code "53") (name "Net-(U2-VDD)") (class "Default")
      (node (ref "C2") (pin "2") (pinfunction "2_2") (pintype "passive"))
      (node (ref "R2") (pin "1") (pinfunction "1_1") (pintype "passive"))
      (node (ref "U2") (pin "9") (pinfunction "VDD_9") (pintype "passive"))
    )
    (net (code "54") (name "Net-(U3-DIN)") (class "Default")
      (node (ref "R14") (pin "2") (pinfunction "2_2") (pintype "passive"))
      (node (ref "U3") (pin "8") (pinfunction "DIN_8") (pintype "passive"))
    )
    (net (code "55") (name "Net-(U3-DOUT)") (class "Default")
      (node (ref "R13") (pin "1") (pinfunction "1_1") (pintype "passive"))
      (node (ref "U3") (pin "10") (pinfunction "DOUT_10") (pintype "passive"))
    )
    (net (code "56") (name "Net-(U3-FDIN)") (class "Default")
      (node (ref "R18") (pin "2") (pinfunction "2_2") (pintype "passive"))
      (node (ref "U3") (pin "6") (pinfunction "FDIN_6") (pintype "passive"))
    )
    (net (code "57") (name "Net-(U3-REXT)") (class "Default")
      (node (ref "R15") (pin "1") (pinfunction "1_1") (pintype "passive"))
      (node (ref "U3") (pin "7") (pinfunction "REXT_7") (pintype "passive"))
    )
    (net (code "58") (name "Net-(U3-VDD)") (class "Default")
      (node (ref "C3") (pin "2") (pinfunction "2_2") (pintype "passive"))
      (node (ref "R11") (pin "1") (pinfunction "1_1") (pintype "passive"))
      (node (ref "U3") (pin "9") (pinfunction "VDD_9") (pintype "passive"))
    )
    (net (code "59") (name "Net-(U4-DIN)") (class "Default")
      (node (ref "R16") (pin "2") (pinfunction "2_2") (pintype "passive"))
      (node (ref "U4") (pin "8") (pinfunction "DIN_8") (pintype "passive"))
    )
    (net (code "60") (name "Net-(U4-DOUT)") (class "Default")
      (node (ref "TP13") (pin "1") (pinfunction "1_1") (pintype "passive"))
      (node (ref "U4") (pin "10") (pinfunction "DOUT_10") (pintype "passive"))
    )
    (net (code "61") (name "Net-(U4-FDIN)") (class "Default")
      (node (ref "R19") (pin "2") (pinfunction "2_2") (pintype "passive"))
      (node (ref "U4") (pin "6") (pinfunction "FDIN_6") (pintype "passive"))
    )
    (net (code "62") (name "Net-(U4-REXT)") (class "Default")
      (node (ref "R17") (pin "1") (pinfunction "1_1") (pintype "passive"))
      (node (ref "U4") (pin "7") (pinfunction "REXT_7") (pintype "passive"))
    )
    (net (code "63") (name "Net-(U4-VDD)") (class "Default")
      (node (ref "C4") (pin "2") (pinfunction "2_2") (pintype "passive"))
      (node (ref "R12") (pin "1") (pinfunction "1_1") (pintype "passive"))
      (node (ref "U4") (pin "9") (pinfunction "VDD_9") (pintype "passive"))
    )
    (net (code "64") (name "unconnected-(U1-W-Pad4)") (class "Default")
      (node (ref "U1") (pin "4") (pinfunction "W_4") (pintype "passive+no_connect"))
    )
    (net (code "65") (name "unconnected-(U2-W-Pad4)") (class "Default")
      (node (ref "U2") (pin "4") (pinfunction "W_4") (pintype "passive+no_connect"))
    )
    (net (code "66") (name "unconnected-(U3-W-Pad4)") (class "Default")
      (node (ref "U3") (pin "4") (pinfunction "W_4") (pintype "passive+no_connect"))
    )
    (net (code "67") (name "unconnected-(U4-W-Pad4)") (class "Default")
      (node (ref "U4") (pin "4") (pinfunction "W_4") (pintype "passive+no_connect"))
    )
  )
)
